# Octal_Reactor_Core_v0.net
KiCad netlist of a schematic drawn in EAGLE
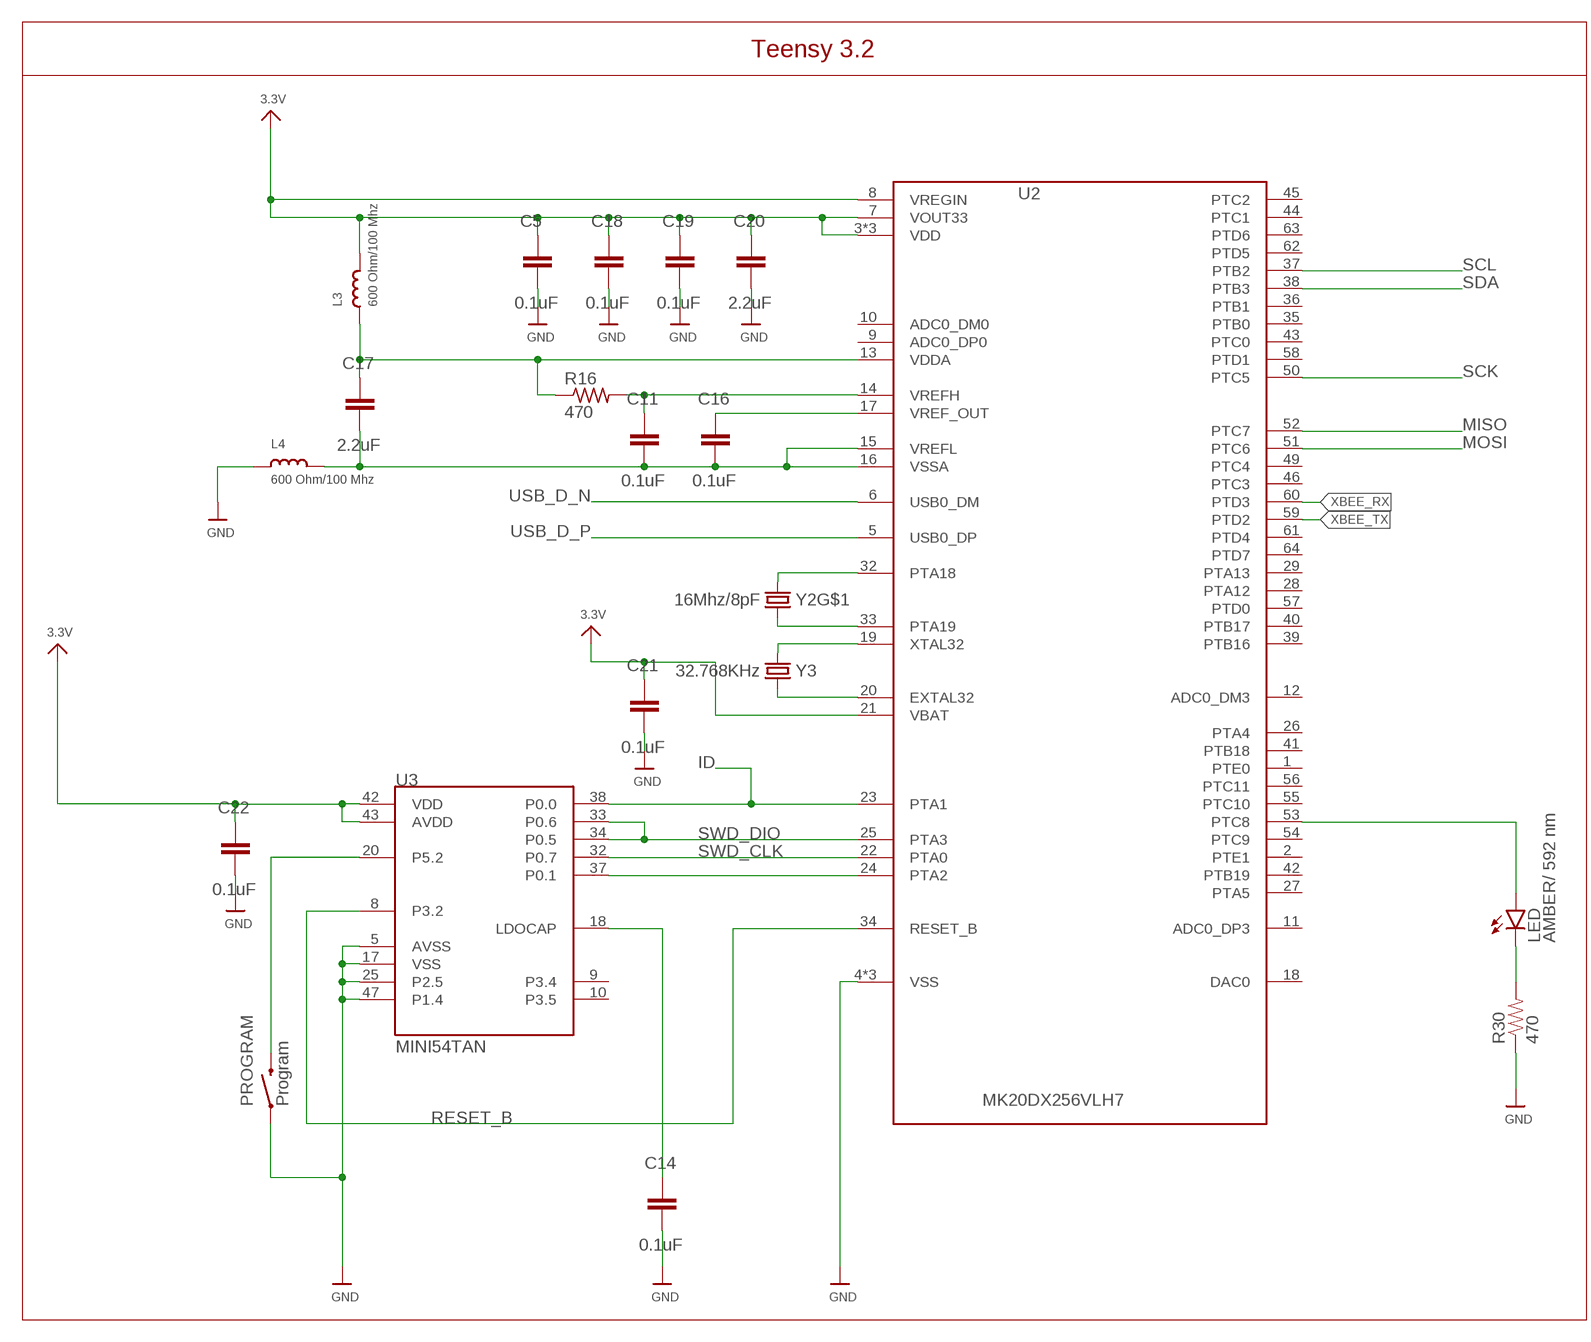
[diagram p0: schematic, sheet 1, part 1 of 2]
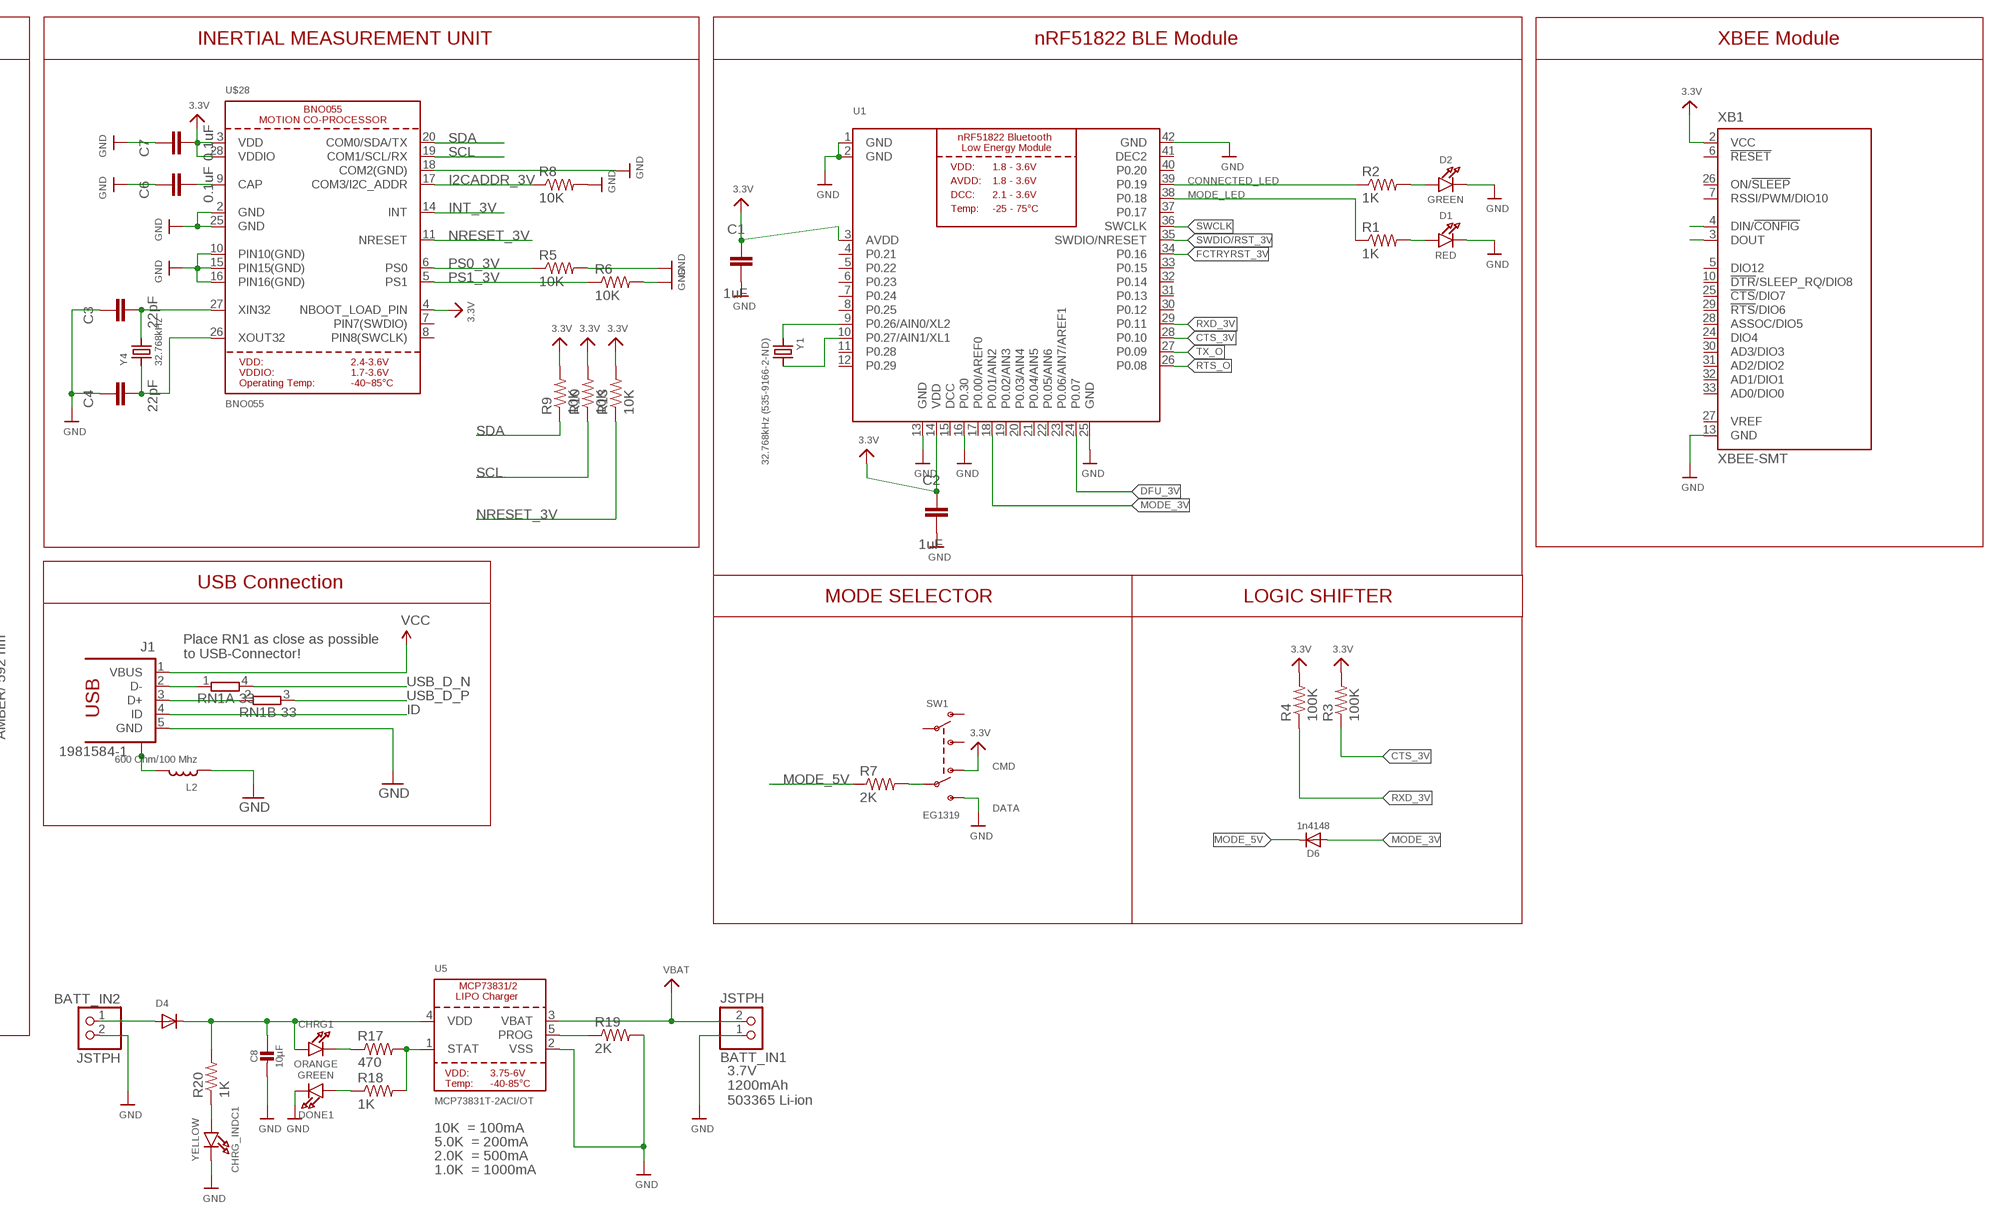
[diagram p1: schematic, sheet 1, part 2 of 2]

(export (version "E")
  (design (tool "Eeschema 10.0.6"))
  (components
    (comp (ref "BATT_IN1")
      (value "JSTPH")
      (footprint "eagle-import:JSTPH2")
      (libsource (lib "eagle-import") (part "JST_2PIN"))
    )
    (comp (ref "BATT_IN2")
      (value "JSTPH")
      (footprint "eagle-import:JSTPH2")
      (libsource (lib "eagle-import") (part "JST_2PIN"))
    )
    (comp (ref "C1")
      (value "1uF")
      (footprint "eagle-import:CAP_0402")
      (fields
        (field (name "DIGIKEY_PART_NUMBER") "311-1014-2-ND")
        (field (name "MANUFACTURER") "Yageo")
        (field (name "MPN") "CC0402JRNPO9BN100")
        (field (name "CREATED_BY") "PCBLayout.com")
      )
      (libsource (lib "eagle-import") (part "CC0402JRNPO9BN100"))
    )
    (comp (ref "C2")
      (value "1uF")
      (footprint "eagle-import:CAP_0402")
      (fields
        (field (name "DIGIKEY_PART_NUMBER") "311-1014-2-ND")
        (field (name "MANUFACTURER") "Yageo")
        (field (name "MPN") "CC0402JRNPO9BN100")
        (field (name "CREATED_BY") "PCBLayout.com")
      )
      (libsource (lib "eagle-import") (part "CC0402JRNPO9BN100"))
    )
    (comp (ref "C3")
      (value "22pF")
      (footprint "eagle-import:CAP_0402")
      (fields
        (field (name "DIGIKEY_PART_NUMBER") "311-1014-2-ND")
        (field (name "MANUFACTURER") "Yageo")
        (field (name "MPN") "CC0402JRNPO9BN100")
        (field (name "CREATED_BY") "PCBLayout.com")
      )
      (libsource (lib "eagle-import") (part "CC0402JRNPO9BN100"))
    )
    (comp (ref "C4")
      (value "22pF")
      (footprint "eagle-import:CAP_0402")
      (fields
        (field (name "DIGIKEY_PART_NUMBER") "311-1014-2-ND")
        (field (name "MANUFACTURER") "Yageo")
        (field (name "MPN") "CC0402JRNPO9BN100")
        (field (name "CREATED_BY") "PCBLayout.com")
      )
      (libsource (lib "eagle-import") (part "CC0402JRNPO9BN100"))
    )
    (comp (ref "C5")
      (value "0.1uF")
      (footprint "eagle-import:CAP_0402")
      (fields
        (field (name "DIGIKEY_PART_NUMBER") "311-1014-2-ND")
        (field (name "MANUFACTURER") "Yageo")
        (field (name "MPN") "CC0402JRNPO9BN100")
        (field (name "CREATED_BY") "PCBLayout.com")
      )
      (libsource (lib "eagle-import") (part "CC0402JRNPO9BN100"))
    )
    (comp (ref "C6")
      (value "0.1uF")
      (footprint "eagle-import:CAP_0402")
      (fields
        (field (name "DIGIKEY_PART_NUMBER") "311-1014-2-ND")
        (field (name "MANUFACTURER") "Yageo")
        (field (name "MPN") "CC0402JRNPO9BN100")
        (field (name "CREATED_BY") "PCBLayout.com")
      )
      (libsource (lib "eagle-import") (part "CC0402JRNPO9BN100"))
    )
    (comp (ref "C7")
      (value "0.1uF")
      (footprint "eagle-import:CAP_0402")
      (fields
        (field (name "DIGIKEY_PART_NUMBER") "311-1014-2-ND")
        (field (name "MANUFACTURER") "Yageo")
        (field (name "MPN") "CC0402JRNPO9BN100")
        (field (name "CREATED_BY") "PCBLayout.com")
      )
      (libsource (lib "eagle-import") (part "CC0402JRNPO9BN100"))
    )
    (comp (ref "C8")
      (value "10µF")
      (footprint "eagle-import:0805-NO")
      (libsource (lib "eagle-import") (part "CAP_CERAMIC0805-NOOUTLINE"))
    )
    (comp (ref "C11")
      (value "0.1uF")
      (footprint "eagle-import:CAP_0402")
      (fields
        (field (name "DIGIKEY_PART_NUMBER") "311-1014-2-ND")
        (field (name "MANUFACTURER") "Yageo")
        (field (name "MPN") "CC0402JRNPO9BN100")
        (field (name "CREATED_BY") "PCBLayout.com")
      )
      (libsource (lib "eagle-import") (part "CC0402JRNPO9BN100"))
    )
    (comp (ref "C14")
      (value "0.1uF")
      (footprint "eagle-import:CAP_0402")
      (fields
        (field (name "DIGIKEY_PART_NUMBER") "311-1014-2-ND")
        (field (name "MANUFACTURER") "Yageo")
        (field (name "MPN") "CC0402JRNPO9BN100")
        (field (name "CREATED_BY") "PCBLayout.com")
      )
      (libsource (lib "eagle-import") (part "CC0402JRNPO9BN100"))
    )
    (comp (ref "C16")
      (value "0.1uF")
      (footprint "eagle-import:CAP_0402")
      (fields
        (field (name "DIGIKEY_PART_NUMBER") "311-1014-2-ND")
        (field (name "MANUFACTURER") "Yageo")
        (field (name "MPN") "CC0402JRNPO9BN100")
        (field (name "CREATED_BY") "PCBLayout.com")
      )
      (libsource (lib "eagle-import") (part "CC0402JRNPO9BN100"))
    )
    (comp (ref "C17")
      (value "2.2uF")
      (footprint "eagle-import:CAP_0402")
      (fields
        (field (name "DIGIKEY_PART_NUMBER") "311-1014-2-ND")
        (field (name "MANUFACTURER") "Yageo")
        (field (name "MPN") "CC0402JRNPO9BN100")
        (field (name "CREATED_BY") "PCBLayout.com")
      )
      (libsource (lib "eagle-import") (part "CC0402JRNPO9BN100"))
    )
    (comp (ref "C18")
      (value "0.1uF")
      (footprint "eagle-import:CAP_0402")
      (fields
        (field (name "DIGIKEY_PART_NUMBER") "311-1014-2-ND")
        (field (name "MANUFACTURER") "Yageo")
        (field (name "MPN") "CC0402JRNPO9BN100")
        (field (name "CREATED_BY") "PCBLayout.com")
      )
      (libsource (lib "eagle-import") (part "CC0402JRNPO9BN100"))
    )
    (comp (ref "C19")
      (value "0.1uF")
      (footprint "eagle-import:CAP_0402")
      (fields
        (field (name "DIGIKEY_PART_NUMBER") "311-1014-2-ND")
        (field (name "MANUFACTURER") "Yageo")
        (field (name "MPN") "CC0402JRNPO9BN100")
        (field (name "CREATED_BY") "PCBLayout.com")
      )
      (libsource (lib "eagle-import") (part "CC0402JRNPO9BN100"))
    )
    (comp (ref "C20")
      (value "2.2uF")
      (footprint "eagle-import:CAP_0402")
      (fields
        (field (name "DIGIKEY_PART_NUMBER") "311-1018-2-ND")
        (field (name "MANUFACTURER") "Yageo")
        (field (name "MPN") "CC0402JRNPO9BN220")
        (field (name "CREATED_BY") "PCBLayout.com")
      )
      (libsource (lib "eagle-import") (part "CC0402JRNPO9BN220"))
    )
    (comp (ref "C21")
      (value "0.1uF")
      (footprint "eagle-import:CAP_0402")
      (fields
        (field (name "DIGIKEY_PART_NUMBER") "311-1014-2-ND")
        (field (name "MANUFACTURER") "Yageo")
        (field (name "MPN") "CC0402JRNPO9BN100")
        (field (name "CREATED_BY") "PCBLayout.com")
      )
      (libsource (lib "eagle-import") (part "CC0402JRNPO9BN100"))
    )
    (comp (ref "C22")
      (value "0.1uF")
      (footprint "eagle-import:CAP_0402")
      (fields
        (field (name "DIGIKEY_PART_NUMBER") "311-1014-2-ND")
        (field (name "MANUFACTURER") "Yageo")
        (field (name "MPN") "CC0402JRNPO9BN100")
        (field (name "CREATED_BY") "PCBLayout.com")
      )
      (libsource (lib "eagle-import") (part "CC0402JRNPO9BN100"))
    )
    (comp (ref "CHRG1")
      (value "ORANGE")
      (footprint "eagle-import:CHIPLED_0805_NOOUTLINE")
      (libsource (lib "eagle-import") (part "LED0805_NOOUTLINE"))
    )
    (comp (ref "CHRG_INDC1")
      (value "YELLOW")
      (footprint "eagle-import:CHIPLED_0805_NOOUTLINE")
      (libsource (lib "eagle-import") (part "LED0805_NOOUTLINE"))
    )
    (comp (ref "D1")
      (value "RED")
      (footprint "eagle-import:CHIPLED_0805_NOOUTLINE")
      (libsource (lib "eagle-import") (part "LED0805_NOOUTLINE"))
    )
    (comp (ref "D2")
      (value "GREEN")
      (footprint "eagle-import:CHIPLED_0805_NOOUTLINE")
      (libsource (lib "eagle-import") (part "LED0805_NOOUTLINE"))
    )
    (comp (ref "D4")
      (value "DIODESOD-123")
      (footprint "eagle-import:SOD-123")
      (libsource (lib "eagle-import") (part "DIODESOD-123"))
    )
    (comp (ref "D6")
      (value "1n4148")
      (footprint "eagle-import:SOD-323")
      (libsource (lib "eagle-import") (part "DIODESOD-323"))
    )
    (comp (ref "DONE1")
      (value "GREEN")
      (footprint "eagle-import:CHIPLED_0805_NOOUTLINE")
      (libsource (lib "eagle-import") (part "LED0805_NOOUTLINE"))
    )
    (comp (ref "J1")
      (value "1981584-1")
      (footprint "eagle-import:1981584-1")
      (fields (field (name "MF") "Hirose") (field (name "MPN") "ZX62-AB-5PA(11) "))
      (libsource (lib "eagle-import") (part "1981584-1"))
    )
    (comp (ref "L2")
      (value "600 Ohm/100 Mhz")
      (footprint "eagle-import:0805")
      (fields (field (name "MF") "Taiyo Yuden") (field (name "MPN") "BK2125HM601-T"))
      (libsource (lib "eagle-import") (part "INDUCTOR-BK2125HM601-T"))
    )
    (comp (ref "L3")
      (value "600 Ohm/100 Mhz")
      (footprint "eagle-import:0805")
      (fields (field (name "MF") "Taiyo Yuden") (field (name "MPN") "BK2125HM601-T"))
      (libsource (lib "eagle-import") (part "INDUCTOR-BK2125HM601-T"))
    )
    (comp (ref "L4")
      (value "600 Ohm/100 Mhz")
      (footprint "eagle-import:0805")
      (fields (field (name "MF") "Taiyo Yuden") (field (name "MPN") "BK2125HM601-T"))
      (libsource (lib "eagle-import") (part "INDUCTOR-BK2125HM601-T"))
    )
    (comp (ref "LED")
      (value "AMBER/ 592 nm")
      (footprint "eagle-import:LED-0603")
      (fields (field (name "MF") "Avago Technologies") (field (name "MPN") "HSMA-C190"))
      (libsource (lib "eagle-import") (part "LED-AMBER"))
    )
    (comp (ref "PROGRAM")
      (value "Program")
      (footprint "eagle-import:TACTILE-SWITCH-1101NE")
      (fields (field (name "MF") "C&K Components") (field (name "MPN") "RS-282G05A3-SM RT"))
      (libsource (lib "eagle-import") (part "SWITCH-MOMENTARY-2-SMD-1101NE"))
    )
    (comp (ref "R1")
      (value "1K")
      (footprint "eagle-import:RES_0402")
      (fields
        (field (name "DIGIKEY_PART_NUMBER") "311-0.0JRTR-ND")
        (field (name "MANUFACTURER") "Yageo")
        (field (name "MPN") "RC0402JR-070RL")
        (field (name "CREATED_BY") "PCBLayout.com")
      )
      (libsource (lib "eagle-import") (part "RC0402JR-070RL"))
    )
    (comp (ref "R2")
      (value "1K")
      (footprint "eagle-import:RES_0402")
      (fields
        (field (name "DIGIKEY_PART_NUMBER") "311-0.0JRTR-ND")
        (field (name "MANUFACTURER") "Yageo")
        (field (name "MPN") "RC0402JR-070RL")
        (field (name "CREATED_BY") "PCBLayout.com")
      )
      (libsource (lib "eagle-import") (part "RC0402JR-070RL"))
    )
    (comp (ref "R3")
      (value "100K")
      (footprint "eagle-import:RES_0402")
      (fields
        (field (name "DIGIKEY_PART_NUMBER") "311-0.0JRTR-ND")
        (field (name "MANUFACTURER") "Yageo")
        (field (name "MPN") "RC0402JR-070RL")
        (field (name "CREATED_BY") "PCBLayout.com")
      )
      (libsource (lib "eagle-import") (part "RC0402JR-070RL"))
    )
    (comp (ref "R4")
      (value "100K")
      (footprint "eagle-import:RES_0402")
      (fields
        (field (name "DIGIKEY_PART_NUMBER") "311-0.0JRTR-ND")
        (field (name "MANUFACTURER") "Yageo")
        (field (name "MPN") "RC0402JR-070RL")
        (field (name "CREATED_BY") "PCBLayout.com")
      )
      (libsource (lib "eagle-import") (part "RC0402JR-070RL"))
    )
    (comp (ref "R5")
      (value "10K")
      (footprint "eagle-import:RES_0402")
      (fields
        (field (name "DIGIKEY_PART_NUMBER") "311-0.0JRTR-ND")
        (field (name "MANUFACTURER") "Yageo")
        (field (name "MPN") "RC0402JR-070RL")
        (field (name "CREATED_BY") "PCBLayout.com")
      )
      (libsource (lib "eagle-import") (part "RC0402JR-070RL"))
    )
    (comp (ref "R6")
      (value "10K")
      (footprint "eagle-import:RES_0402")
      (fields
        (field (name "DIGIKEY_PART_NUMBER") "311-0.0JRTR-ND")
        (field (name "MANUFACTURER") "Yageo")
        (field (name "MPN") "RC0402JR-070RL")
        (field (name "CREATED_BY") "PCBLayout.com")
      )
      (libsource (lib "eagle-import") (part "RC0402JR-070RL"))
    )
    (comp (ref "R7")
      (value "2K")
      (footprint "eagle-import:RES_0402")
      (fields
        (field (name "DIGIKEY_PART_NUMBER") "311-0.0JRTR-ND")
        (field (name "MANUFACTURER") "Yageo")
        (field (name "MPN") "RC0402JR-070RL")
        (field (name "CREATED_BY") "PCBLayout.com")
      )
      (libsource (lib "eagle-import") (part "RC0402JR-070RL"))
    )
    (comp (ref "R8")
      (value "10K")
      (footprint "eagle-import:RES_0402")
      (fields
        (field (name "DIGIKEY_PART_NUMBER") "311-0.0JRTR-ND")
        (field (name "MANUFACTURER") "Yageo")
        (field (name "MPN") "RC0402JR-070RL")
        (field (name "CREATED_BY") "PCBLayout.com")
      )
      (libsource (lib "eagle-import") (part "RC0402JR-070RL"))
    )
    (comp (ref "R9")
      (value "10K")
      (footprint "eagle-import:RES_0402")
      (fields
        (field (name "DIGIKEY_PART_NUMBER") "311-0.0JRTR-ND")
        (field (name "MANUFACTURER") "Yageo")
        (field (name "MPN") "RC0402JR-070RL")
        (field (name "CREATED_BY") "PCBLayout.com")
      )
      (libsource (lib "eagle-import") (part "RC0402JR-070RL"))
    )
    (comp (ref "R10")
      (value "10K")
      (footprint "eagle-import:RES_0402")
      (fields
        (field (name "DIGIKEY_PART_NUMBER") "311-0.0JRTR-ND")
        (field (name "MANUFACTURER") "Yageo")
        (field (name "MPN") "RC0402JR-070RL")
        (field (name "CREATED_BY") "PCBLayout.com")
      )
      (libsource (lib "eagle-import") (part "RC0402JR-070RL"))
    )
    (comp (ref "R13")
      (value "10K")
      (footprint "eagle-import:RES_0402")
      (fields
        (field (name "DIGIKEY_PART_NUMBER") "311-0.0JRTR-ND")
        (field (name "MANUFACTURER") "Yageo")
        (field (name "MPN") "RC0402JR-070RL")
        (field (name "CREATED_BY") "PCBLayout.com")
      )
      (libsource (lib "eagle-import") (part "RC0402JR-070RL"))
    )
    (comp (ref "R16")
      (value "470")
      (footprint "eagle-import:RES_0402")
      (fields
        (field (name "DIGIKEY_PART_NUMBER") "311-0.0JRTR-ND")
        (field (name "MANUFACTURER") "Yageo")
        (field (name "MPN") "RC0402JR-070RL")
        (field (name "CREATED_BY") "PCBLayout.com")
      )
      (libsource (lib "eagle-import") (part "RC0402JR-070RL"))
    )
    (comp (ref "R17")
      (value "470")
      (footprint "eagle-import:RES_0402")
      (fields
        (field (name "DIGIKEY_PART_NUMBER") "311-0.0JRTR-ND")
        (field (name "MANUFACTURER") "Yageo")
        (field (name "MPN") "RC0402JR-070RL")
        (field (name "CREATED_BY") "PCBLayout.com")
      )
      (libsource (lib "eagle-import") (part "RC0402JR-070RL"))
    )
    (comp (ref "R18")
      (value "1K")
      (footprint "eagle-import:RES_0402")
      (fields
        (field (name "DIGIKEY_PART_NUMBER") "311-0.0JRTR-ND")
        (field (name "MANUFACTURER") "Yageo")
        (field (name "MPN") "RC0402JR-070RL")
        (field (name "CREATED_BY") "PCBLayout.com")
      )
      (libsource (lib "eagle-import") (part "RC0402JR-070RL"))
    )
    (comp (ref "R19")
      (value "2K")
      (footprint "eagle-import:RES_0402")
      (fields
        (field (name "DIGIKEY_PART_NUMBER") "311-0.0JRTR-ND")
        (field (name "MANUFACTURER") "Yageo")
        (field (name "MPN") "RC0402JR-070RL")
        (field (name "CREATED_BY") "PCBLayout.com")
      )
      (libsource (lib "eagle-import") (part "RC0402JR-070RL"))
    )
    (comp (ref "R20")
      (value "1K")
      (footprint "eagle-import:RES_0402")
      (fields
        (field (name "DIGIKEY_PART_NUMBER") "311-0.0JRTR-ND")
        (field (name "MANUFACTURER") "Yageo")
        (field (name "MPN") "RC0402JR-070RL")
        (field (name "CREATED_BY") "PCBLayout.com")
      )
      (libsource (lib "eagle-import") (part "RC0402JR-070RL"))
    )
    (comp (ref "R30")
      (value "470")
      (footprint "eagle-import:0603-RES")
      (fields (field (name "MF") "Panasonic") (field (name "MPN") "ERJ-3GEYJ471V"))
      (libsource (lib "eagle-import") (part "RESISTOR-470"))
    )
    (comp (ref "RN1")
      (value "33")
      (footprint "eagle-import:EXB34V")
      (fields (field (name "MF") "Panasonic") (field (name "MPN") "EXB-34V330JV"))
      (libsource (lib "eagle-import") (part "2R-NEXB34V"))
    )
    (comp (ref "SW1")
      (value "EG1319")
      (footprint "eagle-import:EG1390")
      (libsource (lib "eagle-import") (part "SWITCH_DPDTEG1390"))
    )
    (comp (ref "U$28")
      (value "BNO055")
      (footprint "eagle-import:BNO055")
      (libsource (lib "eagle-import") (part "BNO055"))
    )
    (comp (ref "U1")
      (value "NRF51822_MODULE_MDBT40")
      (footprint "eagle-import:BLE_MODULE_RAYTAC_MDBT40")
      (libsource (lib "eagle-import") (part "NRF51822_MODULE_MDBT40"))
    )
    (comp (ref "U2")
      (value "MK20DX256VLH7")
      (footprint "eagle-import:MK20DX256VLH7")
      (fields (field (name "MF") "Freescale"))
      (libsource (lib "eagle-import") (part "MK20DX256VLH7"))
    )
    (comp (ref "U3")
      (value "MINI54TAN")
      (footprint "eagle-import:MINI54TAN")
      (libsource (lib "eagle-import") (part "MINI54TAN"))
    )
    (comp (ref "U5")
      (value "MCP73831T-2ACI/OT")
      (footprint "eagle-import:SOT23-5")
      (libsource (lib "eagle-import") (part "MCP73831/2"))
    )
    (comp (ref "XB1")
      (value "XBEE-SMT")
      (footprint "eagle-import:XBEE-SMT")
      (libsource (lib "eagle-import") (part "XBEE-SMT"))
    )
    (comp (ref "Y1")
      (value "32.768kHz (535-9166-2-ND)")
      (footprint "eagle-import:CRYSTAL_CYL_2X6MM_SMT")
      (libsource (lib "eagle-import") (part "CRYSTAL2.0X6.0_32.768"))
    )
    (comp (ref "Y2")
      (value "16Mhz/8pF")
      (footprint "eagle-import:CRYSTAL-SMD-5X3")
      (fields (field (name "MF") "ECS") (field (name "MPN") "ECS-160-8-30B-CKM"))
      (libsource (lib "eagle-import") (part "CRYSTAL/SMD-5X3-GND16MHZ/8PF"))
    )
    (comp (ref "Y3")
      (value "32.768KHz")
      (footprint "eagle-import:CRYSTAL-TXC-7A")
      (fields (field (name "MF") "Epson Timing") (field (name "MPN") "FC-255 32.7680K-A3"))
      (libsource (lib "eagle-import") (part "CRYSTAL/32.768KHZ/SMD-TXC_7A"))
    )
    (comp (ref "Y4")
      (value "32.768kHz")
      (footprint "eagle-import:CRYSTAL_8X3.8")
      (libsource (lib "eagle-import") (part "CRYSTAL8.0X3.8"))
    )
  )
  (nets
    (net (code "1") (name "/CONNECTED_LED") (class "Default")
      (node (ref "R2") (pin "1") (pinfunction "1_1") (pintype "passive"))
      (node (ref "U1") (pin "39") (pinfunction "P0.19_39") (pintype "bidirectional"))
    )
    (net (code "2") (name "/DCC") (class "Default")
      (node (ref "U1") (pin "15") (pinfunction "DCC_15") (pintype "power_in"))
    )
    (net (code "3") (name "/DEC2") (class "Default")
      (node (ref "U1") (pin "41") (pinfunction "DEC2_41") (pintype "power_in"))
    )
    (net (code "4") (name "/I2CADDR_3V") (class "Default")
      (node (ref "R8") (pin "1") (pinfunction "1_1") (pintype "passive"))
      (node (ref "U$28") (pin "17") (pinfunction "COM3/I2C_ADDR_17") (pintype "bidirectional"))
    )
    (net (code "5") (name "/ID") (class "Default")
      (node (ref "J1") (pin "4") (pinfunction "ID_4") (pintype "passive"))
      (node (ref "U2") (pin "23") (pinfunction "PTA1_23") (pintype "bidirectional"))
      (node (ref "U3") (pin "38") (pinfunction "P0.0_38") (pintype "bidirectional"))
    )
    (net (code "6") (name "/INT_3V") (class "Default")
      (node (ref "U$28") (pin "14") (pinfunction "INT_14") (pintype "output"))
    )
    (net (code "7") (name "/MISO") (class "Default")
      (node (ref "U2") (pin "52") (pinfunction "PTC7_52") (pintype "bidirectional"))
    )
    (net (code "8") (name "/MODE_LED") (class "Default")
      (node (ref "R1") (pin "1") (pinfunction "1_1") (pintype "passive"))
      (node (ref "U1") (pin "38") (pinfunction "P0.18_38") (pintype "bidirectional"))
    )
    (net (code "9") (name "/MOSI") (class "Default")
      (node (ref "U2") (pin "51") (pinfunction "PTC6_51") (pintype "bidirectional"))
    )
    (net (code "10") (name "/NRESET_3V") (class "Default")
      (node (ref "R13") (pin "1") (pinfunction "1_1") (pintype "passive"))
      (node (ref "U$28") (pin "11") (pinfunction "NRESET_11") (pintype "bidirectional"))
    )
    (net (code "11") (name "/PS0_3V") (class "Default")
      (node (ref "R5") (pin "1") (pinfunction "1_1") (pintype "passive"))
      (node (ref "U$28") (pin "6") (pinfunction "PS0_6") (pintype "input"))
    )
    (net (code "12") (name "/PS1_3V") (class "Default")
      (node (ref "R6") (pin "1") (pinfunction "1_1") (pintype "passive"))
      (node (ref "U$28") (pin "5") (pinfunction "PS1_5") (pintype "input"))
    )
    (net (code "13") (name "/RESET_B") (class "Default")
      (node (ref "U2") (pin "34") (pinfunction "RESET_B_34") (pintype "bidirectional"))
      (node (ref "U3") (pin "8") (pinfunction "P3.2_8") (pintype "bidirectional"))
    )
    (net (code "14") (name "/SCK") (class "Default")
      (node (ref "U2") (pin "50") (pinfunction "PTC5_50") (pintype "bidirectional"))
    )
    (net (code "15") (name "/SCL") (class "Default")
      (node (ref "R10") (pin "1") (pinfunction "1_1") (pintype "passive"))
      (node (ref "U$28") (pin "19") (pinfunction "COM1/SCL/RX_19") (pintype "bidirectional"))
      (node (ref "U2") (pin "37") (pinfunction "PTB2_37") (pintype "bidirectional"))
    )
    (net (code "16") (name "/SDA") (class "Default")
      (node (ref "R9") (pin "1") (pinfunction "1_1") (pintype "passive"))
      (node (ref "U$28") (pin "20") (pinfunction "COM0/SDA/TX_20") (pintype "bidirectional"))
      (node (ref "U2") (pin "38") (pinfunction "PTB3_38") (pintype "bidirectional"))
    )
    (net (code "17") (name "/SWD_CLK") (class "Default")
      (node (ref "U2") (pin "22") (pinfunction "PTA0_22") (pintype "bidirectional"))
      (node (ref "U3") (pin "32") (pinfunction "P0.7_32") (pintype "bidirectional"))
    )
    (net (code "18") (name "/SWD_DIO") (class "Default")
      (node (ref "U2") (pin "25") (pinfunction "PTA3_25") (pintype "bidirectional"))
      (node (ref "U3") (pin "33") (pinfunction "P0.6_33") (pintype "bidirectional"))
      (node (ref "U3") (pin "34") (pinfunction "P0.5_34") (pintype "bidirectional"))
    )
    (net (code "19") (name "/USB_D_N") (class "Default")
      (node (ref "RN1") (pin "4") (pinfunction "2_4") (pintype "passive"))
      (node (ref "U2") (pin "6") (pinfunction "USB0_DM_6") (pintype "bidirectional"))
    )
    (net (code "20") (name "/USB_D_P") (class "Default")
      (node (ref "RN1") (pin "3") (pinfunction "2_3") (pintype "passive"))
      (node (ref "U2") (pin "5") (pinfunction "USB0_DP_5") (pintype "bidirectional"))
    )
    (net (code "21") (name "3.3V") (class "Default")
      (node (ref "C1") (pin "1") (pinfunction "1_1") (pintype "passive"))
      (node (ref "C18") (pin "1") (pinfunction "1_1") (pintype "passive"))
      (node (ref "C19") (pin "1") (pinfunction "1_1") (pintype "passive"))
      (node (ref "C2") (pin "1") (pinfunction "1_1") (pintype "passive"))
      (node (ref "C20") (pin "1") (pinfunction "1_1") (pintype "passive"))
      (node (ref "C21") (pin "1") (pinfunction "1_1") (pintype "passive"))
      (node (ref "C22") (pin "1") (pinfunction "1_1") (pintype "passive"))
      (node (ref "C5") (pin "1") (pinfunction "1_1") (pintype "passive"))
      (node (ref "C7") (pin "2") (pinfunction "2_2") (pintype "passive"))
      (node (ref "L3") (pin "2") (pinfunction "2_2") (pintype "passive"))
      (node (ref "R10") (pin "2") (pinfunction "2_2") (pintype "passive"))
      (node (ref "R13") (pin "2") (pinfunction "2_2") (pintype "passive"))
      (node (ref "R3") (pin "2") (pinfunction "2_2") (pintype "passive"))
      (node (ref "R4") (pin "2") (pinfunction "2_2") (pintype "passive"))
      (node (ref "R9") (pin "2") (pinfunction "2_2") (pintype "passive"))
      (node (ref "SW1") (pin "O2") (pinfunction "O2_O2") (pintype "passive"))
      (node (ref "U$28") (pin "28") (pinfunction "VDDIO_28") (pintype "power_in"))
      (node (ref "U$28") (pin "3") (pinfunction "VDD_3") (pintype "power_in"))
      (node (ref "U$28") (pin "4") (pinfunction "NBOOT_LOAD_PIN_4") (pintype "bidirectional"))
      (node (ref "U1") (pin "14") (pinfunction "VDD_14") (pintype "power_in"))
      (node (ref "U1") (pin "3") (pinfunction "AVDD_3") (pintype "power_in"))
      (node (ref "U2") (pin "21") (pinfunction "VBAT_21") (pintype "bidirectional"))
      (node (ref "U2") (pin "3") (pinfunction "VDD_3") (pintype "bidirectional"))
      (node (ref "U2") (pin "30") (pinfunction "VDD_30") (pintype "bidirectional"))
      (node (ref "U2") (pin "48") (pinfunction "VDD_48") (pintype "bidirectional"))
      (node (ref "U2") (pin "7") (pinfunction "VOUT33_7") (pintype "bidirectional"))
      (node (ref "U2") (pin "8") (pinfunction "VREGIN_8") (pintype "bidirectional"))
      (node (ref "U3") (pin "42") (pinfunction "VDD_42") (pintype "bidirectional"))
      (node (ref "U3") (pin "43") (pinfunction "AVDD_43") (pintype "bidirectional"))
      (node (ref "XB1") (pin "2") (pinfunction "VCC_2") (pintype "power_in"))
    )
    (net (code "22") (name "CTS_3V") (class "Default")
      (node (ref "R3") (pin "1") (pinfunction "1_1") (pintype "passive"))
      (node (ref "U1") (pin "28") (pinfunction "P0.10_28") (pintype "bidirectional"))
    )
    (net (code "23") (name "DFU_3V") (class "Default")
      (node (ref "U1") (pin "24") (pinfunction "P0.07_24") (pintype "bidirectional"))
    )
    (net (code "24") (name "FCTRYRST_3V") (class "Default")
      (node (ref "U1") (pin "34") (pinfunction "P0.16_34") (pintype "bidirectional"))
    )
    (net (code "25") (name "GND") (class "Default")
      (node (ref "BATT_IN1") (pin "1") (pinfunction "1_1") (pintype "passive"))
      (node (ref "BATT_IN2") (pin "2") (pinfunction "2_2") (pintype "passive"))
      (node (ref "C1") (pin "2") (pinfunction "2_2") (pintype "passive"))
      (node (ref "C14") (pin "2") (pinfunction "2_2") (pintype "passive"))
      (node (ref "C18") (pin "2") (pinfunction "2_2") (pintype "passive"))
      (node (ref "C19") (pin "2") (pinfunction "2_2") (pintype "passive"))
      (node (ref "C2") (pin "2") (pinfunction "2_2") (pintype "passive"))
      (node (ref "C20") (pin "2") (pinfunction "2_2") (pintype "passive"))
      (node (ref "C21") (pin "2") (pinfunction "2_2") (pintype "passive"))
      (node (ref "C22") (pin "2") (pinfunction "2_2") (pintype "passive"))
      (node (ref "C3") (pin "1") (pinfunction "1_1") (pintype "passive"))
      (node (ref "C4") (pin "1") (pinfunction "1_1") (pintype "passive"))
      (node (ref "C5") (pin "2") (pinfunction "2_2") (pintype "passive"))
      (node (ref "C6") (pin "1") (pinfunction "1_1") (pintype "passive"))
      (node (ref "C7") (pin "1") (pinfunction "1_1") (pintype "passive"))
      (node (ref "C8") (pin "2") (pinfunction "2_2") (pintype "passive"))
      (node (ref "CHRG_INDC1") (pin "C") (pinfunction "C_C") (pintype "passive"))
      (node (ref "D1") (pin "C") (pinfunction "C_C") (pintype "passive"))
      (node (ref "D2") (pin "C") (pinfunction "C_C") (pintype "passive"))
      (node (ref "DONE1") (pin "C") (pinfunction "C_C") (pintype "passive"))
      (node (ref "J1") (pin "5") (pinfunction "GND_5") (pintype "passive"))
      (node (ref "L2") (pin "1") (pinfunction "1_1") (pintype "passive"))
      (node (ref "L4") (pin "1") (pinfunction "1_1") (pintype "passive"))
      (node (ref "PROGRAM") (pin "P$1") (pinfunction "1_P$1") (pintype "passive"))
      (node (ref "R19") (pin "2") (pinfunction "2_2") (pintype "passive"))
      (node (ref "R30") (pin "1") (pinfunction "1_1") (pintype "passive"))
      (node (ref "R5") (pin "2") (pinfunction "2_2") (pintype "passive"))
      (node (ref "R6") (pin "2") (pinfunction "2_2") (pintype "passive"))
      (node (ref "R8") (pin "2") (pinfunction "2_2") (pintype "passive"))
      (node (ref "SW1") (pin "S2") (pinfunction "S2_S2") (pintype "passive"))
      (node (ref "U$28") (pin "10") (pinfunction "PIN10(GND)_10") (pintype "bidirectional"))
      (node (ref "U$28") (pin "15") (pinfunction "PIN15(GND)_15") (pintype "bidirectional"))
      (node (ref "U$28") (pin "16") (pinfunction "PIN16(GND)_16") (pintype "bidirectional"))
      (node (ref "U$28") (pin "18") (pinfunction "COM2(GND)_18") (pintype "bidirectional"))
      (node (ref "U$28") (pin "2") (pinfunction "GND_2") (pintype "power_in"))
      (node (ref "U$28") (pin "25") (pinfunction "GND_25") (pintype "power_in"))
      (node (ref "U1") (pin "1") (pinfunction "GND_1") (pintype "power_in"))
      (node (ref "U1") (pin "13") (pinfunction "GND_13") (pintype "power_in"))
      (node (ref "U1") (pin "16") (pinfunction "P0.30_16") (pintype "bidirectional"))
      (node (ref "U1") (pin "2") (pinfunction "GND_2") (pintype "power_in"))
      (node (ref "U1") (pin "25") (pinfunction "GND_25") (pintype "power_in"))
      (node (ref "U1") (pin "42") (pinfunction "GND_42") (pintype "power_in"))
      (node (ref "U2") (pin "31") (pinfunction "VSS_31") (pintype "bidirectional"))
      (node (ref "U2") (pin "4") (pinfunction "VSS_4") (pintype "bidirectional"))
      (node (ref "U2") (pin "47") (pinfunction "VSS_47") (pintype "bidirectional"))
      (node (ref "U3") (pin "17") (pinfunction "VSS_17") (pintype "bidirectional"))
      (node (ref "U3") (pin "25") (pinfunction "P2.5_25") (pintype "bidirectional"))
      (node (ref "U3") (pin "47") (pinfunction "P1.4_47") (pintype "bidirectional"))
      (node (ref "U3") (pin "5") (pinfunction "AVSS_5") (pintype "bidirectional"))
      (node (ref "U5") (pin "2") (pinfunction "VSS_2") (pintype "power_in"))
      (node (ref "XB1") (pin "13") (pinfunction "GND_13") (pintype "power_in"))
    )
    (net (code "26") (name "MODE_3V") (class "Default")
      (node (ref "D6") (pin "A") (pinfunction "A_A") (pintype "passive"))
      (node (ref "U1") (pin "18") (pinfunction "P0.01/AIN2_18") (pintype "bidirectional"))
    )
    (net (code "27") (name "MODE_5V") (class "Default")
      (node (ref "D6") (pin "C") (pinfunction "C_C") (pintype "passive"))
      (node (ref "R7") (pin "1") (pinfunction "1_1") (pintype "passive"))
    )
    (net (code "28") (name "Net-(BATT_IN2-Pad1)") (class "Default")
      (node (ref "BATT_IN2") (pin "1") (pinfunction "1_1") (pintype "passive"))
      (node (ref "D4") (pin "A") (pinfunction "A_A") (pintype "passive"))
    )
    (net (code "29") (name "Net-(CHRG1-PadC)") (class "Default")
      (node (ref "CHRG1") (pin "C") (pinfunction "C_C") (pintype "passive"))
      (node (ref "R17") (pin "1") (pinfunction "1_1") (pintype "passive"))
    )
    (net (code "30") (name "Net-(CHRG_INDC1-PadA)") (class "Default")
      (node (ref "CHRG_INDC1") (pin "A") (pinfunction "A_A") (pintype "passive"))
      (node (ref "R20") (pin "1") (pinfunction "1_1") (pintype "passive"))
    )
    (net (code "31") (name "Net-(D1-PadA)") (class "Default")
      (node (ref "D1") (pin "A") (pinfunction "A_A") (pintype "passive"))
      (node (ref "R1") (pin "2") (pinfunction "2_2") (pintype "passive"))
    )
    (net (code "32") (name "Net-(D2-PadA)") (class "Default")
      (node (ref "D2") (pin "A") (pinfunction "A_A") (pintype "passive"))
      (node (ref "R2") (pin "2") (pinfunction "2_2") (pintype "passive"))
    )
    (net (code "33") (name "Net-(DONE1-PadA)") (class "Default")
      (node (ref "DONE1") (pin "A") (pinfunction "A_A") (pintype "passive"))
      (node (ref "R18") (pin "1") (pinfunction "1_1") (pintype "passive"))
    )
    (net (code "34") (name "Net-(J1-D+)") (class "Default")
      (node (ref "J1") (pin "3") (pinfunction "D+_3") (pintype "passive"))
      (node (ref "RN1") (pin "2") (pinfunction "1_2") (pintype "passive"))
    )
    (net (code "35") (name "Net-(J1-D-)") (class "Default")
      (node (ref "J1") (pin "2") (pinfunction "D-_2") (pintype "passive"))
      (node (ref "RN1") (pin "1") (pinfunction "1_1") (pintype "passive"))
    )
    (net (code "36") (name "Net-(J1-PadS1)") (class "Default")
      (node (ref "J1") (pin "S1") (pinfunction "S1_S1") (pintype "passive"))
      (node (ref "J1") (pin "S2") (pinfunction "S2_S2") (pintype "passive"))
      (node (ref "J1") (pin "S3") (pinfunction "S3_S3") (pintype "passive"))
      (node (ref "J1") (pin "S4") (pinfunction "S4_S4") (pintype "passive"))
      (node (ref "L2") (pin "2") (pinfunction "2_2") (pintype "passive"))
    )
    (net (code "37") (name "Net-(LED-PadC)") (class "Default")
      (node (ref "LED") (pin "C") (pinfunction "C_C") (pintype "passive"))
      (node (ref "R30") (pin "2") (pinfunction "2_2") (pintype "passive"))
    )
    (net (code "38") (name "Net-(PROGRAM-2)") (class "Default")
      (node (ref "PROGRAM") (pin "P$2") (pinfunction "2_P$2") (pintype "passive"))
      (node (ref "U3") (pin "20") (pinfunction "P5.2_20") (pintype "bidirectional"))
    )
    (net (code "39") (name "Net-(R7-Pad2)") (class "Default")
      (node (ref "R7") (pin "2") (pinfunction "2_2") (pintype "passive"))
      (node (ref "SW1") (pin "P2") (pinfunction "P2_P2") (pintype "passive"))
    )
    (net (code "40") (name "Net-(U$28-CAP)") (class "Default")
      (node (ref "C6") (pin "2") (pinfunction "2_2") (pintype "passive"))
      (node (ref "U$28") (pin "9") (pinfunction "CAP_9") (pintype "passive"))
    )
    (net (code "41") (name "Net-(U$28-XIN32)") (class "Default")
      (node (ref "C3") (pin "2") (pinfunction "2_2") (pintype "passive"))
      (node (ref "U$28") (pin "27") (pinfunction "XIN32_27") (pintype "input"))
      (node (ref "Y4") (pin "P$4") (pinfunction "2_P$4") (pintype "passive"))
    )
    (net (code "42") (name "Net-(U$28-XOUT32)") (class "Default")
      (node (ref "C4") (pin "2") (pinfunction "2_2") (pintype "passive"))
      (node (ref "U$28") (pin "26") (pinfunction "XOUT32_26") (pintype "output"))
      (node (ref "Y4") (pin "P$1") (pinfunction "1_P$1") (pintype "passive"))
    )
    (net (code "43") (name "Net-(U1-P0.26{slash}AIN0{slash}XL2)") (class "Default")
      (node (ref "U1") (pin "9") (pinfunction "P0.26/AIN0/XL2_9") (pintype "bidirectional"))
      (node (ref "Y1") (pin "1") (pinfunction "1_1") (pintype "passive"))
    )
    (net (code "44") (name "Net-(U1-P0.27{slash}AIN1{slash}XL1)") (class "Default")
      (node (ref "U1") (pin "10") (pinfunction "P0.27/AIN1/XL1_10") (pintype "bidirectional"))
      (node (ref "Y1") (pin "2") (pinfunction "2_2") (pintype "passive"))
    )
    (net (code "45") (name "Net-(U2-EXTAL32)") (class "Default")
      (node (ref "U2") (pin "20") (pinfunction "EXTAL32_20") (pintype "bidirectional"))
      (node (ref "Y3") (pin "P$1") (pinfunction "1_P$1") (pintype "passive"))
    )
    (net (code "46") (name "Net-(U2-PTA2)") (class "Default")
      (node (ref "U2") (pin "24") (pinfunction "PTA2_24") (pintype "bidirectional"))
      (node (ref "U3") (pin "37") (pinfunction "P0.1_37") (pintype "bidirectional"))
    )
    (net (code "47") (name "Net-(U2-PTA18)") (class "Default")
      (node (ref "U2") (pin "32") (pinfunction "PTA18_32") (pintype "bidirectional"))
      (node (ref "Y2") (pin "3") (pinfunction "2_3") (pintype "passive"))
    )
    (net (code "48") (name "Net-(U2-PTA19)") (class "Default")
      (node (ref "U2") (pin "33") (pinfunction "PTA19_33") (pintype "bidirectional"))
      (node (ref "Y2") (pin "1") (pinfunction "1_1") (pintype "passive"))
    )
    (net (code "49") (name "Net-(U2-PTC8)") (class "Default")
      (node (ref "LED") (pin "A") (pinfunction "A_A") (pintype "passive"))
      (node (ref "U2") (pin "53") (pinfunction "PTC8_53") (pintype "bidirectional"))
    )
    (net (code "50") (name "Net-(U2-VDDA)") (class "Default")
      (node (ref "C17") (pin "1") (pinfunction "1_1") (pintype "passive"))
      (node (ref "L3") (pin "1") (pinfunction "1_1") (pintype "passive"))
      (node (ref "R16") (pin "1") (pinfunction "1_1") (pintype "passive"))
      (node (ref "U2") (pin "13") (pinfunction "VDDA_13") (pintype "bidirectional"))
    )
    (net (code "51") (name "Net-(U2-VREFH)") (class "Default")
      (node (ref "C11") (pin "1") (pinfunction "1_1") (pintype "passive"))
      (node (ref "R16") (pin "2") (pinfunction "2_2") (pintype "passive"))
      (node (ref "U2") (pin "14") (pinfunction "VREFH_14") (pintype "bidirectional"))
    )
    (net (code "52") (name "Net-(U2-VREFL)") (class "Default")
      (node (ref "C11") (pin "2") (pinfunction "2_2") (pintype "passive"))
      (node (ref "C16") (pin "2") (pinfunction "2_2") (pintype "passive"))
      (node (ref "C17") (pin "2") (pinfunction "2_2") (pintype "passive"))
      (node (ref "L4") (pin "2") (pinfunction "2_2") (pintype "passive"))
      (node (ref "U2") (pin "15") (pinfunction "VREFL_15") (pintype "bidirectional"))
      (node (ref "U2") (pin "16") (pinfunction "VSSA_16") (pintype "bidirectional"))
    )
    (net (code "53") (name "Net-(U2-VREF_OUT)") (class "Default")
      (node (ref "C16") (pin "1") (pinfunction "1_1") (pintype "passive"))
      (node (ref "U2") (pin "17") (pinfunction "VREF_OUT_17") (pintype "bidirectional"))
    )
    (net (code "54") (name "Net-(U2-XTAL32)") (class "Default")
      (node (ref "U2") (pin "19") (pinfunction "XTAL32_19") (pintype "bidirectional"))
      (node (ref "Y3") (pin "P$2") (pinfunction "2_P$2") (pintype "passive"))
    )
    (net (code "55") (name "Net-(U3-LDOCAP)") (class "Default")
      (node (ref "C14") (pin "1") (pinfunction "1_1") (pintype "passive"))
      (node (ref "U3") (pin "18") (pinfunction "LDOCAP_18") (pintype "bidirectional"))
    )
    (net (code "56") (name "Net-(U5-PROG)") (class "Default")
      (node (ref "R19") (pin "1") (pinfunction "1_1") (pintype "passive"))
      (node (ref "U5") (pin "5") (pinfunction "PROG_5") (pintype "input"))
    )
    (net (code "57") (name "Net-(U5-STAT)") (class "Default")
      (node (ref "R17") (pin "2") (pinfunction "2_2") (pintype "passive"))
      (node (ref "R18") (pin "2") (pinfunction "2_2") (pintype "passive"))
      (node (ref "U5") (pin "1") (pinfunction "STAT_1") (pintype "output"))
    )
    (net (code "58") (name "Net-(U5-VDD)") (class "Default")
      (node (ref "C8") (pin "1") (pinfunction "1_1") (pintype "passive"))
      (node (ref "CHRG1") (pin "A") (pinfunction "A_A") (pintype "passive"))
      (node (ref "D4") (pin "C") (pinfunction "C_C") (pintype "passive"))
      (node (ref "R20") (pin "2") (pinfunction "2_2") (pintype "passive"))
      (node (ref "U5") (pin "4") (pinfunction "VDD_4") (pintype "power_in"))
    )
    (net (code "59") (name "RTS_O") (class "Default")
      (node (ref "U1") (pin "26") (pinfunction "P0.08_26") (pintype "bidirectional"))
    )
    (net (code "60") (name "RXD_3V") (class "Default")
      (node (ref "R4") (pin "1") (pinfunction "1_1") (pintype "passive"))
      (node (ref "U1") (pin "29") (pinfunction "P0.11_29") (pintype "bidirectional"))
    )
    (net (code "61") (name "SWCLK") (class "Default")
      (node (ref "U1") (pin "36") (pinfunction "SWCLK_36") (pintype "bidirectional"))
    )
    (net (code "62") (name "SWDIO{slash}RST_3V") (class "Default")
      (node (ref "U1") (pin "35") (pinfunction "SWDIO/NRESET_35") (pintype "bidirectional"))
    )
    (net (code "63") (name "TX_O") (class "Default")
      (node (ref "U1") (pin "27") (pinfunction "P0.09_27") (pintype "bidirectional"))
    )
    (net (code "64") (name "VBAT") (class "Default")
      (node (ref "BATT_IN1") (pin "2") (pinfunction "2_2") (pintype "passive"))
      (node (ref "U5") (pin "3") (pinfunction "VBAT_3") (pintype "power_in"))
    )
    (net (code "65") (name "VCC") (class "Default")
      (node (ref "J1") (pin "1") (pinfunction "VBUS_1") (pintype "passive"))
    )
    (net (code "66") (name "XBEE_RX") (class "Default")
      (node (ref "U2") (pin "60") (pinfunction "PTD3_60") (pintype "bidirectional"))
    )
    (net (code "67") (name "XBEE_TX") (class "Default")
      (node (ref "U2") (pin "59") (pinfunction "PTD2_59") (pintype "bidirectional"))
    )
    (net (code "68") (name "unconnected-(SW1-PadO1)") (class "Default")
      (node (ref "SW1") (pin "O1") (pinfunction "O1_O1") (pintype "passive"))
    )
    (net (code "69") (name "unconnected-(SW1-PadP1)") (class "Default")
      (node (ref "SW1") (pin "P1") (pinfunction "P1_P1") (pintype "passive"))
    )
    (net (code "70") (name "unconnected-(SW1-PadS1)") (class "Default")
      (node (ref "SW1") (pin "S1") (pinfunction "S1_S1") (pintype "passive"))
    )
    (net (code "71") (name "unconnected-(U$28-PIN7(SWDIO)-Pad7)") (class "Default")
      (node (ref "U$28") (pin "7") (pinfunction "PIN7(SWDIO)_7") (pintype "bidirectional"))
    )
    (net (code "72") (name "unconnected-(U$28-PIN8(SWCLK)-Pad8)") (class "Default")
      (node (ref "U$28") (pin "8") (pinfunction "PIN8(SWCLK)_8") (pintype "bidirectional"))
    )
    (net (code "73") (name "unconnected-(U1-P0.00{slash}AREF0-Pad17)") (class "Default")
      (node (ref "U1") (pin "17") (pinfunction "P0.00/AREF0_17") (pintype "bidirectional"))
    )
    (net (code "74") (name "unconnected-(U1-P0.02{slash}AIN3-Pad19)") (class "Default")
      (node (ref "U1") (pin "19") (pinfunction "P0.02/AIN3_19") (pintype "bidirectional"))
    )
    (net (code "75") (name "unconnected-(U1-P0.03{slash}AIN4-Pad20)") (class "Default")
      (node (ref "U1") (pin "20") (pinfunction "P0.03/AIN4_20") (pintype "bidirectional"))
    )
    (net (code "76") (name "unconnected-(U1-P0.04{slash}AIN5-Pad21)") (class "Default")
      (node (ref "U1") (pin "21") (pinfunction "P0.04/AIN5_21") (pintype "bidirectional"))
    )
    (net (code "77") (name "unconnected-(U1-P0.05{slash}AIN6-Pad22)") (class "Default")
      (node (ref "U1") (pin "22") (pinfunction "P0.05/AIN6_22") (pintype "bidirectional"))
    )
    (net (code "78") (name "unconnected-(U1-P0.06{slash}AIN7{slash}AREF1-Pad23)") (class "Default")
      (node (ref "U1") (pin "23") (pinfunction "P0.06/AIN7/AREF1_23") (pintype "bidirectional"))
    )
    (net (code "79") (name "unconnected-(U1-P0.12-Pad30)") (class "Default")
      (node (ref "U1") (pin "30") (pinfunction "P0.12_30") (pintype "bidirectional"))
    )
    (net (code "80") (name "unconnected-(U1-P0.13-Pad31)") (class "Default")
      (node (ref "U1") (pin "31") (pinfunction "P0.13_31") (pintype "bidirectional"))
    )
    (net (code "81") (name "unconnected-(U1-P0.14-Pad32)") (class "Default")
      (node (ref "U1") (pin "32") (pinfunction "P0.14_32") (pintype "bidirectional"))
    )
    (net (code "82") (name "unconnected-(U1-P0.15-Pad33)") (class "Default")
      (node (ref "U1") (pin "33") (pinfunction "P0.15_33") (pintype "bidirectional"))
    )
    (net (code "83") (name "unconnected-(U1-P0.17-Pad37)") (class "Default")
      (node (ref "U1") (pin "37") (pinfunction "P0.17_37") (pintype "bidirectional"))
    )
    (net (code "84") (name "unconnected-(U1-P0.20-Pad40)") (class "Default")
      (node (ref "U1") (pin "40") (pinfunction "P0.20_40") (pintype "bidirectional"))
    )
    (net (code "85") (name "unconnected-(U1-P0.21-Pad4)") (class "Default")
      (node (ref "U1") (pin "4") (pinfunction "P0.21_4") (pintype "bidirectional"))
    )
    (net (code "86") (name "unconnected-(U1-P0.22-Pad5)") (class "Default")
      (node (ref "U1") (pin "5") (pinfunction "P0.22_5") (pintype "bidirectional"))
    )
    (net (code "87") (name "unconnected-(U1-P0.23-Pad6)") (class "Default")
      (node (ref "U1") (pin "6") (pinfunction "P0.23_6") (pintype "bidirectional"))
    )
    (net (code "88") (name "unconnected-(U1-P0.24-Pad7)") (class "Default")
      (node (ref "U1") (pin "7") (pinfunction "P0.24_7") (pintype "bidirectional"))
    )
    (net (code "89") (name "unconnected-(U1-P0.25-Pad8)") (class "Default")
      (node (ref "U1") (pin "8") (pinfunction "P0.25_8") (pintype "bidirectional"))
    )
    (net (code "90") (name "unconnected-(U1-P0.28-Pad11)") (class "Default")
      (node (ref "U1") (pin "11") (pinfunction "P0.28_11") (pintype "bidirectional"))
    )
    (net (code "91") (name "unconnected-(U1-P0.29-Pad12)") (class "Default")
      (node (ref "U1") (pin "12") (pinfunction "P0.29_12") (pintype "bidirectional"))
    )
    (net (code "92") (name "unconnected-(U2-ADC0_DM0-Pad10)") (class "Default")
      (node (ref "U2") (pin "10") (pinfunction "ADC0_DM0_10") (pintype "bidirectional"))
    )
    (net (code "93") (name "unconnected-(U2-ADC0_DM3-Pad12)") (class "Default")
      (node (ref "U2") (pin "12") (pinfunction "ADC0_DM3_12") (pintype "bidirectional"))
    )
    (net (code "94") (name "unconnected-(U2-ADC0_DP0-Pad9)") (class "Default")
      (node (ref "U2") (pin "9") (pinfunction "ADC0_DP0_9") (pintype "bidirectional"))
    )
    (net (code "95") (name "unconnected-(U2-ADC0_DP3-Pad11)") (class "Default")
      (node (ref "U2") (pin "11") (pinfunction "ADC0_DP3_11") (pintype "bidirectional"))
    )
    (net (code "96") (name "unconnected-(U2-DAC0-Pad18)") (class "Default")
      (node (ref "U2") (pin "18") (pinfunction "DAC0_18") (pintype "bidirectional"))
    )
    (net (code "97") (name "unconnected-(U2-PTA4-Pad26)") (class "Default")
      (node (ref "U2") (pin "26") (pinfunction "PTA4_26") (pintype "bidirectional"))
    )
    (net (code "98") (name "unconnected-(U2-PTA5-Pad27)") (class "Default")
      (node (ref "U2") (pin "27") (pinfunction "PTA5_27") (pintype "bidirectional"))
    )
    (net (code "99") (name "unconnected-(U2-PTA12-Pad28)") (class "Default")
      (node (ref "U2") (pin "28") (pinfunction "PTA12_28") (pintype "bidirectional"))
    )
    (net (code "100") (name "unconnected-(U2-PTA13-Pad29)") (class "Default")
      (node (ref "U2") (pin "29") (pinfunction "PTA13_29") (pintype "bidirectional"))
    )
    (net (code "101") (name "unconnected-(U2-PTB0-Pad35)") (class "Default")
      (node (ref "U2") (pin "35") (pinfunction "PTB0_35") (pintype "bidirectional"))
    )
    (net (code "102") (name "unconnected-(U2-PTB1-Pad36)") (class "Default")
      (node (ref "U2") (pin "36") (pinfunction "PTB1_36") (pintype "bidirectional"))
    )
    (net (code "103") (name "unconnected-(U2-PTB16-Pad39)") (class "Default")
      (node (ref "U2") (pin "39") (pinfunction "PTB16_39") (pintype "bidirectional"))
    )
    (net (code "104") (name "unconnected-(U2-PTB17-Pad40)") (class "Default")
      (node (ref "U2") (pin "40") (pinfunction "PTB17_40") (pintype "bidirectional"))
    )
    (net (code "105") (name "unconnected-(U2-PTB18-Pad41)") (class "Default")
      (node (ref "U2") (pin "41") (pinfunction "PTB18_41") (pintype "bidirectional"))
    )
    (net (code "106") (name "unconnected-(U2-PTB19-Pad42)") (class "Default")
      (node (ref "U2") (pin "42") (pinfunction "PTB19_42") (pintype "bidirectional"))
    )
    (net (code "107") (name "unconnected-(U2-PTC0-Pad43)") (class "Default")
      (node (ref "U2") (pin "43") (pinfunction "PTC0_43") (pintype "bidirectional"))
    )
    (net (code "108") (name "unconnected-(U2-PTC1-Pad44)") (class "Default")
      (node (ref "U2") (pin "44") (pinfunction "PTC1_44") (pintype "bidirectional"))
    )
    (net (code "109") (name "unconnected-(U2-PTC2-Pad45)") (class "Default")
      (node (ref "U2") (pin "45") (pinfunction "PTC2_45") (pintype "bidirectional"))
    )
    (net (code "110") (name "unconnected-(U2-PTC3-Pad46)") (class "Default")
      (node (ref "U2") (pin "46") (pinfunction "PTC3_46") (pintype "bidirectional"))
    )
    (net (code "111") (name "unconnected-(U2-PTC4-Pad49)") (class "Default")
      (node (ref "U2") (pin "49") (pinfunction "PTC4_49") (pintype "bidirectional"))
    )
    (net (code "112") (name "unconnected-(U2-PTC9-Pad54)") (class "Default")
      (node (ref "U2") (pin "54") (pinfunction "PTC9_54") (pintype "bidirectional"))
    )
    (net (code "113") (name "unconnected-(U2-PTC10-Pad55)") (class "Default")
      (node (ref "U2") (pin "55") (pinfunction "PTC10_55") (pintype "bidirectional"))
    )
    (net (code "114") (name "unconnected-(U2-PTC11-Pad56)") (class "Default")
      (node (ref "U2") (pin "56") (pinfunction "PTC11_56") (pintype "bidirectional"))
    )
    (net (code "115") (name "unconnected-(U2-PTD0-Pad57)") (class "Default")
      (node (ref "U2") (pin "57") (pinfunction "PTD0_57") (pintype "bidirectional"))
    )
    (net (code "116") (name "unconnected-(U2-PTD1-Pad58)") (class "Default")
      (node (ref "U2") (pin "58") (pinfunction "PTD1_58") (pintype "bidirectional"))
    )
    (net (code "117") (name "unconnected-(U2-PTD4-Pad61)") (class "Default")
      (node (ref "U2") (pin "61") (pinfunction "PTD4_61") (pintype "bidirectional"))
    )
    (net (code "118") (name "unconnected-(U2-PTD5-Pad62)") (class "Default")
      (node (ref "U2") (pin "62") (pinfunction "PTD5_62") (pintype "bidirectional"))
    )
    (net (code "119") (name "unconnected-(U2-PTD6-Pad63)") (class "Default")
      (node (ref "U2") (pin "63") (pinfunction "PTD6_63") (pintype "bidirectional"))
    )
    (net (code "120") (name "unconnected-(U2-PTD7-Pad64)") (class "Default")
      (node (ref "U2") (pin "64") (pinfunction "PTD7_64") (pintype "bidirectional"))
    )
    (net (code "121") (name "unconnected-(U2-PTE0-Pad1)") (class "Default")
      (node (ref "U2") (pin "1") (pinfunction "PTE0_1") (pintype "bidirectional"))
    )
    (net (code "122") (name "unconnected-(U2-PTE1-Pad2)") (class "Default")
      (node (ref "U2") (pin "2") (pinfunction "PTE1_2") (pintype "bidirectional"))
    )
    (net (code "123") (name "unconnected-(U3-P3.4-Pad9)") (class "Default")
      (node (ref "U3") (pin "9") (pinfunction "P3.4_9") (pintype "bidirectional"))
    )
    (net (code "124") (name "unconnected-(U3-P3.5-Pad10)") (class "Default")
      (node (ref "U3") (pin "10") (pinfunction "P3.5_10") (pintype "bidirectional"))
    )
    (net (code "125") (name "unconnected-(XB1-AD0{slash}DIO0-Pad33)") (class "Default")
      (node (ref "XB1") (pin "33") (pinfunction "AD0/DIO0_33") (pintype "bidirectional"))
    )
    (net (code "126") (name "unconnected-(XB1-AD1{slash}DIO1-Pad32)") (class "Default")
      (node (ref "XB1") (pin "32") (pinfunction "AD1/DIO1_32") (pintype "bidirectional"))
    )
    (net (code "127") (name "unconnected-(XB1-AD2{slash}DIO2-Pad31)") (class "Default")
      (node (ref "XB1") (pin "31") (pinfunction "AD2/DIO2_31") (pintype "bidirectional"))
    )
    (net (code "128") (name "unconnected-(XB1-AD3{slash}DIO3-Pad30)") (class "Default")
      (node (ref "XB1") (pin "30") (pinfunction "AD3/DIO3_30") (pintype "bidirectional"))
    )
    (net (code "129") (name "unconnected-(XB1-ASSOC{slash}DIO5-Pad28)") (class "Default")
      (node (ref "XB1") (pin "28") (pinfunction "ASSOC/DIO5_28") (pintype "bidirectional"))
    )
    (net (code "130") (name "unconnected-(XB1-DIN{slash}~{CONFIG}-Pad4)") (class "Default")
      (node (ref "XB1") (pin "4") (pinfunction "DIN/~{CONFIG}_4") (pintype "input"))
    )
    (net (code "131") (name "unconnected-(XB1-DIO4-Pad24)") (class "Default")
      (node (ref "XB1") (pin "24") (pinfunction "DIO4_24") (pintype "bidirectional"))
    )
    (net (code "132") (name "unconnected-(XB1-DIO12-Pad5)") (class "Default")
      (node (ref "XB1") (pin "5") (pinfunction "DIO12_5") (pintype "bidirectional"))
    )
    (net (code "133") (name "unconnected-(XB1-DOUT-Pad3)") (class "Default")
      (node (ref "XB1") (pin "3") (pinfunction "DOUT_3") (pintype "output"))
    )
    (net (code "134") (name "unconnected-(XB1-ON{slash}~{SLEEP}-Pad26)") (class "Default")
      (node (ref "XB1") (pin "26") (pinfunction "ON/~{SLEEP}_26") (pintype "output"))
    )
    (net (code "135") (name "unconnected-(XB1-RSSI{slash}PWM{slash}DIO10-Pad7)") (class "Default")
      (node (ref "XB1") (pin "7") (pinfunction "RSSI/PWM/DIO10_7") (pintype "output"))
    )
    (net (code "136") (name "unconnected-(XB1-VREF-Pad27)") (class "Default")
      (node (ref "XB1") (pin "27") (pinfunction "VREF_27") (pintype "input"))
    )
    (net (code "137") (name "unconnected-(XB1-~{CTS}{slash}DIO7-Pad25)") (class "Default")
      (node (ref "XB1") (pin "25") (pinfunction "~{CTS}/DIO7_25") (pintype "bidirectional"))
    )
    (net (code "138") (name "unconnected-(XB1-~{DTR}{slash}SLEEP_RQ{slash}DIO8-Pad10)") (class "Default")
      (node (ref "XB1") (pin "10") (pinfunction "~{DTR}/SLEEP_RQ/DIO8_10") (pintype "bidirectional"))
    )
    (net (code "139") (name "unconnected-(XB1-~{RESET}-Pad6)") (class "Default")
      (node (ref "XB1") (pin "6") (pinfunction "~{RESET}_6") (pintype "input"))
    )
    (net (code "140") (name "unconnected-(XB1-~{RTS}{slash}DIO6-Pad29)") (class "Default")
      (node (ref "XB1") (pin "29") (pinfunction "~{RTS}/DIO6_29") (pintype "bidirectional"))
    )
  )
)
